# ALU.net
KiCad netlist of a schematic drawn in Altium Designer
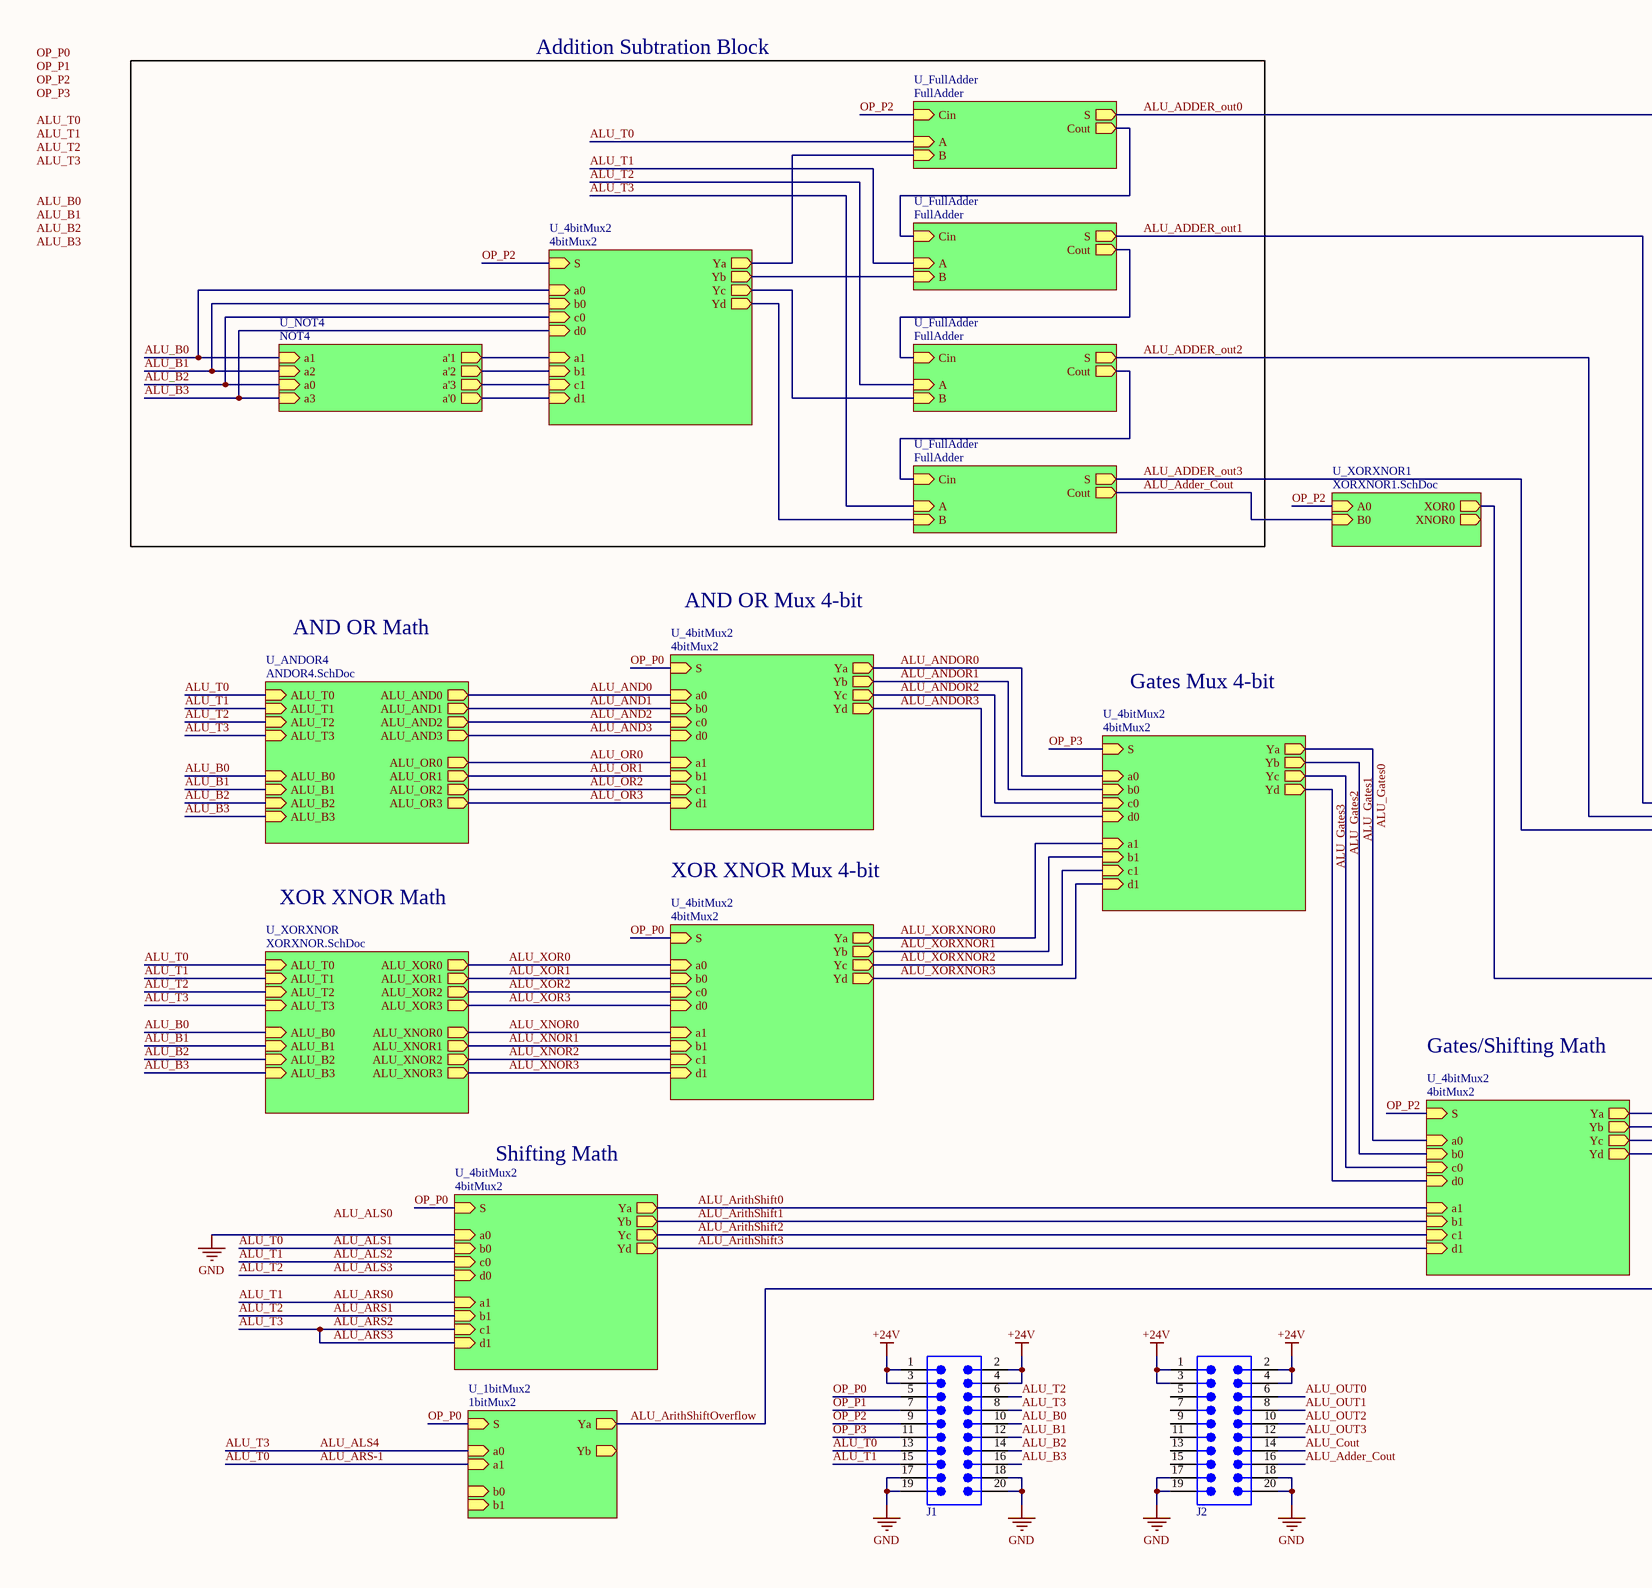
[diagram p0: ALU.SchDoc, left]
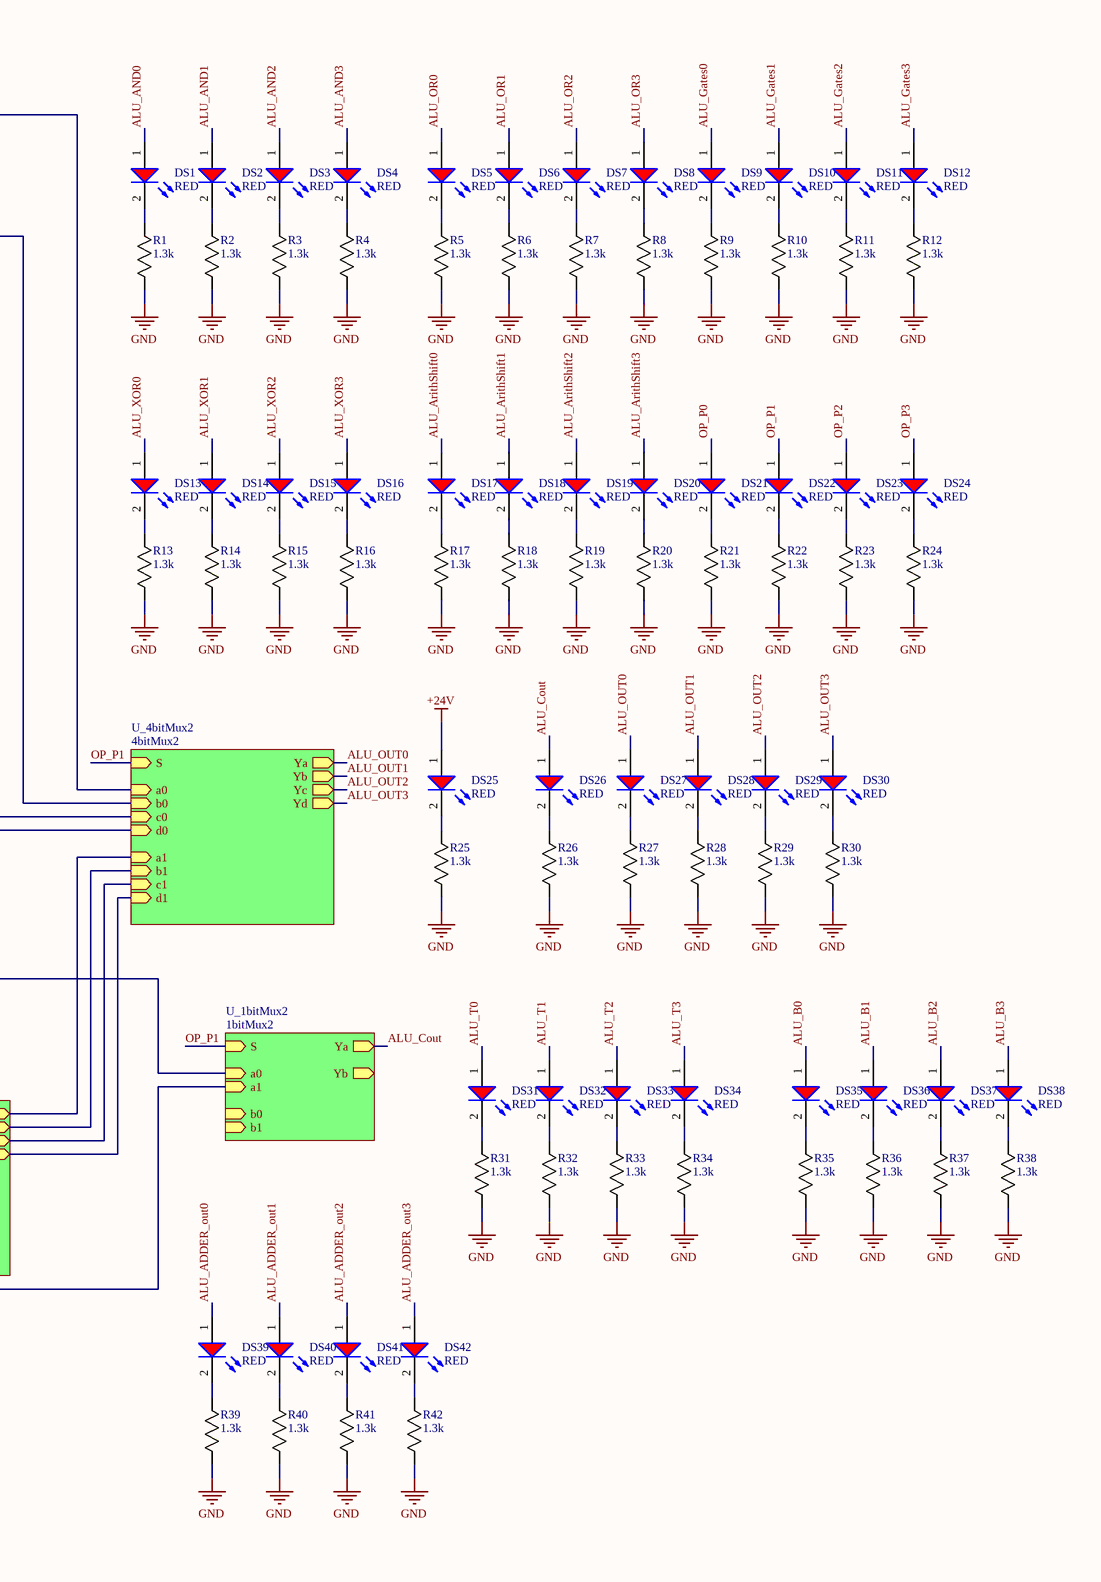
[diagram p1: ALU.SchDoc, right]

(export (version "E")
  (design (tool "Eeschema 10.0.6"))
  (components
    (comp (ref "DS1")
      (value "RED")
      (footprint "LED RED 151051RS11000")
      (description "WL-TMRC Red Color Diffused 5 mm Round Through Hole LED")
      (fields
        (field (name "MANUFACTURER") "Wurth Elektronik")
        (field (name "MANUFACTURER PART NUMBER") "151051RS11000")
      )
      (libsource (lib "Schlib1") (part "LED RED 151051RS11000"))
    )
    (comp (ref "DS2")
      (value "RED")
      (footprint "LED RED 151051RS11000")
      (description "WL-TMRC Red Color Diffused 5 mm Round Through Hole LED")
      (fields
        (field (name "MANUFACTURER") "Wurth Elektronik")
        (field (name "MANUFACTURER PART NUMBER") "151051RS11000")
      )
      (libsource (lib "Schlib1") (part "LED RED 151051RS11000"))
    )
    (comp (ref "DS3")
      (value "RED")
      (footprint "LED RED 151051RS11000")
      (description "WL-TMRC Red Color Diffused 5 mm Round Through Hole LED")
      (fields
        (field (name "MANUFACTURER") "Wurth Elektronik")
        (field (name "MANUFACTURER PART NUMBER") "151051RS11000")
      )
      (libsource (lib "Schlib1") (part "LED RED 151051RS11000"))
    )
    (comp (ref "DS4")
      (value "RED")
      (footprint "LED RED 151051RS11000")
      (description "WL-TMRC Red Color Diffused 5 mm Round Through Hole LED")
      (fields
        (field (name "MANUFACTURER") "Wurth Elektronik")
        (field (name "MANUFACTURER PART NUMBER") "151051RS11000")
      )
      (libsource (lib "Schlib1") (part "LED RED 151051RS11000"))
    )
    (comp (ref "DS5")
      (value "RED")
      (footprint "LED RED 151051RS11000")
      (description "WL-TMRC Red Color Diffused 5 mm Round Through Hole LED")
      (fields
        (field (name "MANUFACTURER") "Wurth Elektronik")
        (field (name "MANUFACTURER PART NUMBER") "151051RS11000")
      )
      (libsource (lib "Schlib1") (part "LED RED 151051RS11000"))
    )
    (comp (ref "DS6")
      (value "RED")
      (footprint "LED RED 151051RS11000")
      (description "WL-TMRC Red Color Diffused 5 mm Round Through Hole LED")
      (fields
        (field (name "MANUFACTURER") "Wurth Elektronik")
        (field (name "MANUFACTURER PART NUMBER") "151051RS11000")
      )
      (libsource (lib "Schlib1") (part "LED RED 151051RS11000"))
    )
    (comp (ref "DS7")
      (value "RED")
      (footprint "LED RED 151051RS11000")
      (description "WL-TMRC Red Color Diffused 5 mm Round Through Hole LED")
      (fields
        (field (name "MANUFACTURER") "Wurth Elektronik")
        (field (name "MANUFACTURER PART NUMBER") "151051RS11000")
      )
      (libsource (lib "Schlib1") (part "LED RED 151051RS11000"))
    )
    (comp (ref "DS8")
      (value "RED")
      (footprint "LED RED 151051RS11000")
      (description "WL-TMRC Red Color Diffused 5 mm Round Through Hole LED")
      (fields
        (field (name "MANUFACTURER") "Wurth Elektronik")
        (field (name "MANUFACTURER PART NUMBER") "151051RS11000")
      )
      (libsource (lib "Schlib1") (part "LED RED 151051RS11000"))
    )
    (comp (ref "DS9")
      (value "RED")
      (footprint "LED RED 151051RS11000")
      (description "WL-TMRC Red Color Diffused 5 mm Round Through Hole LED")
      (fields
        (field (name "MANUFACTURER") "Wurth Elektronik")
        (field (name "MANUFACTURER PART NUMBER") "151051RS11000")
      )
      (libsource (lib "Schlib1") (part "LED RED 151051RS11000"))
    )
    (comp (ref "DS10")
      (value "RED")
      (footprint "LED RED 151051RS11000")
      (description "WL-TMRC Red Color Diffused 5 mm Round Through Hole LED")
      (fields
        (field (name "MANUFACTURER") "Wurth Elektronik")
        (field (name "MANUFACTURER PART NUMBER") "151051RS11000")
      )
      (libsource (lib "Schlib1") (part "LED RED 151051RS11000"))
    )
    (comp (ref "DS11")
      (value "RED")
      (footprint "LED RED 151051RS11000")
      (description "WL-TMRC Red Color Diffused 5 mm Round Through Hole LED")
      (fields
        (field (name "MANUFACTURER") "Wurth Elektronik")
        (field (name "MANUFACTURER PART NUMBER") "151051RS11000")
      )
      (libsource (lib "Schlib1") (part "LED RED 151051RS11000"))
    )
    (comp (ref "DS12")
      (value "RED")
      (footprint "LED RED 151051RS11000")
      (description "WL-TMRC Red Color Diffused 5 mm Round Through Hole LED")
      (fields
        (field (name "MANUFACTURER") "Wurth Elektronik")
        (field (name "MANUFACTURER PART NUMBER") "151051RS11000")
      )
      (libsource (lib "Schlib1") (part "LED RED 151051RS11000"))
    )
    (comp (ref "DS13")
      (value "RED")
      (footprint "LED RED 151051RS11000")
      (description "WL-TMRC Red Color Diffused 5 mm Round Through Hole LED")
      (fields
        (field (name "MANUFACTURER") "Wurth Elektronik")
        (field (name "MANUFACTURER PART NUMBER") "151051RS11000")
      )
      (libsource (lib "Schlib1") (part "LED RED 151051RS11000"))
    )
    (comp (ref "DS14")
      (value "RED")
      (footprint "LED RED 151051RS11000")
      (description "WL-TMRC Red Color Diffused 5 mm Round Through Hole LED")
      (fields
        (field (name "MANUFACTURER") "Wurth Elektronik")
        (field (name "MANUFACTURER PART NUMBER") "151051RS11000")
      )
      (libsource (lib "Schlib1") (part "LED RED 151051RS11000"))
    )
    (comp (ref "DS15")
      (value "RED")
      (footprint "LED RED 151051RS11000")
      (description "WL-TMRC Red Color Diffused 5 mm Round Through Hole LED")
      (fields
        (field (name "MANUFACTURER") "Wurth Elektronik")
        (field (name "MANUFACTURER PART NUMBER") "151051RS11000")
      )
      (libsource (lib "Schlib1") (part "LED RED 151051RS11000"))
    )
    (comp (ref "DS16")
      (value "RED")
      (footprint "LED RED 151051RS11000")
      (description "WL-TMRC Red Color Diffused 5 mm Round Through Hole LED")
      (fields
        (field (name "MANUFACTURER") "Wurth Elektronik")
        (field (name "MANUFACTURER PART NUMBER") "151051RS11000")
      )
      (libsource (lib "Schlib1") (part "LED RED 151051RS11000"))
    )
    (comp (ref "DS17")
      (value "RED")
      (footprint "LED RED 151051RS11000")
      (description "WL-TMRC Red Color Diffused 5 mm Round Through Hole LED")
      (fields
        (field (name "MANUFACTURER") "Wurth Elektronik")
        (field (name "MANUFACTURER PART NUMBER") "151051RS11000")
      )
      (libsource (lib "Schlib1") (part "LED RED 151051RS11000"))
    )
    (comp (ref "DS18")
      (value "RED")
      (footprint "LED RED 151051RS11000")
      (description "WL-TMRC Red Color Diffused 5 mm Round Through Hole LED")
      (fields
        (field (name "MANUFACTURER") "Wurth Elektronik")
        (field (name "MANUFACTURER PART NUMBER") "151051RS11000")
      )
      (libsource (lib "Schlib1") (part "LED RED 151051RS11000"))
    )
    (comp (ref "DS19")
      (value "RED")
      (footprint "LED RED 151051RS11000")
      (description "WL-TMRC Red Color Diffused 5 mm Round Through Hole LED")
      (fields
        (field (name "MANUFACTURER") "Wurth Elektronik")
        (field (name "MANUFACTURER PART NUMBER") "151051RS11000")
      )
      (libsource (lib "Schlib1") (part "LED RED 151051RS11000"))
    )
    (comp (ref "DS20")
      (value "RED")
      (footprint "LED RED 151051RS11000")
      (description "WL-TMRC Red Color Diffused 5 mm Round Through Hole LED")
      (fields
        (field (name "MANUFACTURER") "Wurth Elektronik")
        (field (name "MANUFACTURER PART NUMBER") "151051RS11000")
      )
      (libsource (lib "Schlib1") (part "LED RED 151051RS11000"))
    )
    (comp (ref "DS21")
      (value "RED")
      (footprint "LED RED 151051RS11000")
      (description "WL-TMRC Red Color Diffused 5 mm Round Through Hole LED")
      (fields
        (field (name "MANUFACTURER") "Wurth Elektronik")
        (field (name "MANUFACTURER PART NUMBER") "151051RS11000")
      )
      (libsource (lib "Schlib1") (part "LED RED 151051RS11000"))
    )
    (comp (ref "DS22")
      (value "RED")
      (footprint "LED RED 151051RS11000")
      (description "WL-TMRC Red Color Diffused 5 mm Round Through Hole LED")
      (fields
        (field (name "MANUFACTURER") "Wurth Elektronik")
        (field (name "MANUFACTURER PART NUMBER") "151051RS11000")
      )
      (libsource (lib "Schlib1") (part "LED RED 151051RS11000"))
    )
    (comp (ref "DS23")
      (value "RED")
      (footprint "LED RED 151051RS11000")
      (description "WL-TMRC Red Color Diffused 5 mm Round Through Hole LED")
      (fields
        (field (name "MANUFACTURER") "Wurth Elektronik")
        (field (name "MANUFACTURER PART NUMBER") "151051RS11000")
      )
      (libsource (lib "Schlib1") (part "LED RED 151051RS11000"))
    )
    (comp (ref "DS24")
      (value "RED")
      (footprint "LED RED 151051RS11000")
      (description "WL-TMRC Red Color Diffused 5 mm Round Through Hole LED")
      (fields
        (field (name "MANUFACTURER") "Wurth Elektronik")
        (field (name "MANUFACTURER PART NUMBER") "151051RS11000")
      )
      (libsource (lib "Schlib1") (part "LED RED 151051RS11000"))
    )
    (comp (ref "DS25")
      (value "RED")
      (footprint "LED RED 151051RS11000")
      (description "WL-TMRC Red Color Diffused 5 mm Round Through Hole LED")
      (fields
        (field (name "MANUFACTURER") "Wurth Elektronik")
        (field (name "MANUFACTURER PART NUMBER") "151051RS11000")
      )
      (libsource (lib "Schlib1") (part "LED RED 151051RS11000"))
    )
    (comp (ref "DS26")
      (value "RED")
      (footprint "LED RED 151051RS11000")
      (description "WL-TMRC Red Color Diffused 5 mm Round Through Hole LED")
      (fields
        (field (name "MANUFACTURER") "Wurth Elektronik")
        (field (name "MANUFACTURER PART NUMBER") "151051RS11000")
      )
      (libsource (lib "Schlib1") (part "LED RED 151051RS11000"))
    )
    (comp (ref "DS27")
      (value "RED")
      (footprint "LED RED 151051RS11000")
      (description "WL-TMRC Red Color Diffused 5 mm Round Through Hole LED")
      (fields
        (field (name "MANUFACTURER") "Wurth Elektronik")
        (field (name "MANUFACTURER PART NUMBER") "151051RS11000")
      )
      (libsource (lib "Schlib1") (part "LED RED 151051RS11000"))
    )
    (comp (ref "DS28")
      (value "RED")
      (footprint "LED RED 151051RS11000")
      (description "WL-TMRC Red Color Diffused 5 mm Round Through Hole LED")
      (fields
        (field (name "MANUFACTURER") "Wurth Elektronik")
        (field (name "MANUFACTURER PART NUMBER") "151051RS11000")
      )
      (libsource (lib "Schlib1") (part "LED RED 151051RS11000"))
    )
    (comp (ref "DS29")
      (value "RED")
      (footprint "LED RED 151051RS11000")
      (description "WL-TMRC Red Color Diffused 5 mm Round Through Hole LED")
      (fields
        (field (name "MANUFACTURER") "Wurth Elektronik")
        (field (name "MANUFACTURER PART NUMBER") "151051RS11000")
      )
      (libsource (lib "Schlib1") (part "LED RED 151051RS11000"))
    )
    (comp (ref "DS30")
      (value "RED")
      (footprint "LED RED 151051RS11000")
      (description "WL-TMRC Red Color Diffused 5 mm Round Through Hole LED")
      (fields
        (field (name "MANUFACTURER") "Wurth Elektronik")
        (field (name "MANUFACTURER PART NUMBER") "151051RS11000")
      )
      (libsource (lib "Schlib1") (part "LED RED 151051RS11000"))
    )
    (comp (ref "DS31")
      (value "RED")
      (footprint "LED RED 151051RS11000")
      (description "WL-TMRC Red Color Diffused 5 mm Round Through Hole LED")
      (fields
        (field (name "MANUFACTURER") "Wurth Elektronik")
        (field (name "MANUFACTURER PART NUMBER") "151051RS11000")
      )
      (libsource (lib "Schlib1") (part "LED RED 151051RS11000"))
    )
    (comp (ref "DS32")
      (value "RED")
      (footprint "LED RED 151051RS11000")
      (description "WL-TMRC Red Color Diffused 5 mm Round Through Hole LED")
      (fields
        (field (name "MANUFACTURER") "Wurth Elektronik")
        (field (name "MANUFACTURER PART NUMBER") "151051RS11000")
      )
      (libsource (lib "Schlib1") (part "LED RED 151051RS11000"))
    )
    (comp (ref "DS33")
      (value "RED")
      (footprint "LED RED 151051RS11000")
      (description "WL-TMRC Red Color Diffused 5 mm Round Through Hole LED")
      (fields
        (field (name "MANUFACTURER") "Wurth Elektronik")
        (field (name "MANUFACTURER PART NUMBER") "151051RS11000")
      )
      (libsource (lib "Schlib1") (part "LED RED 151051RS11000"))
    )
    (comp (ref "DS34")
      (value "RED")
      (footprint "LED RED 151051RS11000")
      (description "WL-TMRC Red Color Diffused 5 mm Round Through Hole LED")
      (fields
        (field (name "MANUFACTURER") "Wurth Elektronik")
        (field (name "MANUFACTURER PART NUMBER") "151051RS11000")
      )
      (libsource (lib "Schlib1") (part "LED RED 151051RS11000"))
    )
    (comp (ref "DS35")
      (value "RED")
      (footprint "LED RED 151051RS11000")
      (description "WL-TMRC Red Color Diffused 5 mm Round Through Hole LED")
      (fields
        (field (name "MANUFACTURER") "Wurth Elektronik")
        (field (name "MANUFACTURER PART NUMBER") "151051RS11000")
      )
      (libsource (lib "Schlib1") (part "LED RED 151051RS11000"))
    )
    (comp (ref "DS36")
      (value "RED")
      (footprint "LED RED 151051RS11000")
      (description "WL-TMRC Red Color Diffused 5 mm Round Through Hole LED")
      (fields
        (field (name "MANUFACTURER") "Wurth Elektronik")
        (field (name "MANUFACTURER PART NUMBER") "151051RS11000")
      )
      (libsource (lib "Schlib1") (part "LED RED 151051RS11000"))
    )
    (comp (ref "DS37")
      (value "RED")
      (footprint "LED RED 151051RS11000")
      (description "WL-TMRC Red Color Diffused 5 mm Round Through Hole LED")
      (fields
        (field (name "MANUFACTURER") "Wurth Elektronik")
        (field (name "MANUFACTURER PART NUMBER") "151051RS11000")
      )
      (libsource (lib "Schlib1") (part "LED RED 151051RS11000"))
    )
    (comp (ref "DS38")
      (value "RED")
      (footprint "LED RED 151051RS11000")
      (description "WL-TMRC Red Color Diffused 5 mm Round Through Hole LED")
      (fields
        (field (name "MANUFACTURER") "Wurth Elektronik")
        (field (name "MANUFACTURER PART NUMBER") "151051RS11000")
      )
      (libsource (lib "Schlib1") (part "LED RED 151051RS11000"))
    )
    (comp (ref "DS39")
      (value "RED")
      (footprint "LED RED 151051RS11000")
      (description "WL-TMRC Red Color Diffused 5 mm Round Through Hole LED")
      (fields
        (field (name "MANUFACTURER") "Wurth Elektronik")
        (field (name "MANUFACTURER PART NUMBER") "151051RS11000")
      )
      (libsource (lib "Schlib1") (part "LED RED 151051RS11000"))
    )
    (comp (ref "DS40")
      (value "RED")
      (footprint "LED RED 151051RS11000")
      (description "WL-TMRC Red Color Diffused 5 mm Round Through Hole LED")
      (fields
        (field (name "MANUFACTURER") "Wurth Elektronik")
        (field (name "MANUFACTURER PART NUMBER") "151051RS11000")
      )
      (libsource (lib "Schlib1") (part "LED RED 151051RS11000"))
    )
    (comp (ref "DS41")
      (value "RED")
      (footprint "LED RED 151051RS11000")
      (description "WL-TMRC Red Color Diffused 5 mm Round Through Hole LED")
      (fields
        (field (name "MANUFACTURER") "Wurth Elektronik")
        (field (name "MANUFACTURER PART NUMBER") "151051RS11000")
      )
      (libsource (lib "Schlib1") (part "LED RED 151051RS11000"))
    )
    (comp (ref "DS42")
      (value "RED")
      (footprint "LED RED 151051RS11000")
      (description "WL-TMRC Red Color Diffused 5 mm Round Through Hole LED")
      (fields
        (field (name "MANUFACTURER") "Wurth Elektronik")
        (field (name "MANUFACTURER PART NUMBER") "151051RS11000")
      )
      (libsource (lib "Schlib1") (part "LED RED 151051RS11000"))
    )
    (comp (ref "J1")
      (value "Con 61202021621")
      (footprint "Con 61202021621")
      (description "WR-BHD Straight Male, Box Header, Through Hole, 2 Rows, 20 Contacts, 2.54mm Pitch")
      (fields
        (field (name "MANUFACTURER") "Wurth Elektronik")
        (field (name "MANUFACTURER PART NUMBER") "61202021621")
      )
      (libsource (lib "Schlib1") (part "Con 61202021621"))
    )
    (comp (ref "J2")
      (value "Con 61202021621")
      (footprint "Con 61202021621")
      (description "WR-BHD Straight Male, Box Header, Through Hole, 2 Rows, 20 Contacts, 2.54mm Pitch")
      (fields
        (field (name "MANUFACTURER") "Wurth Elektronik")
        (field (name "MANUFACTURER PART NUMBER") "61202021621")
      )
      (libsource (lib "Schlib1") (part "Con 61202021621"))
    )
    (comp (ref "R1")
      (value "1.3k")
      (footprint "RES 2512")
      (description "Res Thick Film 2512 1.3K Ohm 1% 1W ±100ppm/C Pad SMD Automotive T/R RMCF2512FT1K30")
      (fields
        (field (name "MANUFACTURER") "Stackpole Electronics")
        (field (name "MANUFACTURER PART NUMBER") "RMCF2512FT1K30")
      )
      (libsource (lib "Schlib1") (part "RES 1.3k 2512 1W"))
    )
    (comp (ref "R2")
      (value "1.3k")
      (footprint "RES 2512")
      (description "Res Thick Film 2512 1.3K Ohm 1% 1W ±100ppm/C Pad SMD Automotive T/R RMCF2512FT1K30")
      (fields
        (field (name "MANUFACTURER") "Stackpole Electronics")
        (field (name "MANUFACTURER PART NUMBER") "RMCF2512FT1K30")
      )
      (libsource (lib "Schlib1") (part "RES 1.3k 2512 1W"))
    )
    (comp (ref "R3")
      (value "1.3k")
      (footprint "RES 2512")
      (description "Res Thick Film 2512 1.3K Ohm 1% 1W ±100ppm/C Pad SMD Automotive T/R RMCF2512FT1K30")
      (fields
        (field (name "MANUFACTURER") "Stackpole Electronics")
        (field (name "MANUFACTURER PART NUMBER") "RMCF2512FT1K30")
      )
      (libsource (lib "Schlib1") (part "RES 1.3k 2512 1W"))
    )
    (comp (ref "R4")
      (value "1.3k")
      (footprint "RES 2512")
      (description "Res Thick Film 2512 1.3K Ohm 1% 1W ±100ppm/C Pad SMD Automotive T/R RMCF2512FT1K30")
      (fields
        (field (name "MANUFACTURER") "Stackpole Electronics")
        (field (name "MANUFACTURER PART NUMBER") "RMCF2512FT1K30")
      )
      (libsource (lib "Schlib1") (part "RES 1.3k 2512 1W"))
    )
    (comp (ref "R5")
      (value "1.3k")
      (footprint "RES 2512")
      (description "Res Thick Film 2512 1.3K Ohm 1% 1W ±100ppm/C Pad SMD Automotive T/R RMCF2512FT1K30")
      (fields
        (field (name "MANUFACTURER") "Stackpole Electronics")
        (field (name "MANUFACTURER PART NUMBER") "RMCF2512FT1K30")
      )
      (libsource (lib "Schlib1") (part "RES 1.3k 2512 1W"))
    )
    (comp (ref "R6")
      (value "1.3k")
      (footprint "RES 2512")
      (description "Res Thick Film 2512 1.3K Ohm 1% 1W ±100ppm/C Pad SMD Automotive T/R RMCF2512FT1K30")
      (fields
        (field (name "MANUFACTURER") "Stackpole Electronics")
        (field (name "MANUFACTURER PART NUMBER") "RMCF2512FT1K30")
      )
      (libsource (lib "Schlib1") (part "RES 1.3k 2512 1W"))
    )
    (comp (ref "R7")
      (value "1.3k")
      (footprint "RES 2512")
      (description "Res Thick Film 2512 1.3K Ohm 1% 1W ±100ppm/C Pad SMD Automotive T/R RMCF2512FT1K30")
      (fields
        (field (name "MANUFACTURER") "Stackpole Electronics")
        (field (name "MANUFACTURER PART NUMBER") "RMCF2512FT1K30")
      )
      (libsource (lib "Schlib1") (part "RES 1.3k 2512 1W"))
    )
    (comp (ref "R8")
      (value "1.3k")
      (footprint "RES 2512")
      (description "Res Thick Film 2512 1.3K Ohm 1% 1W ±100ppm/C Pad SMD Automotive T/R RMCF2512FT1K30")
      (fields
        (field (name "MANUFACTURER") "Stackpole Electronics")
        (field (name "MANUFACTURER PART NUMBER") "RMCF2512FT1K30")
      )
      (libsource (lib "Schlib1") (part "RES 1.3k 2512 1W"))
    )
    (comp (ref "R9")
      (value "1.3k")
      (footprint "RES 2512")
      (description "Res Thick Film 2512 1.3K Ohm 1% 1W ±100ppm/C Pad SMD Automotive T/R RMCF2512FT1K30")
      (fields
        (field (name "MANUFACTURER") "Stackpole Electronics")
        (field (name "MANUFACTURER PART NUMBER") "RMCF2512FT1K30")
      )
      (libsource (lib "Schlib1") (part "RES 1.3k 2512 1W"))
    )
    (comp (ref "R10")
      (value "1.3k")
      (footprint "RES 2512")
      (description "Res Thick Film 2512 1.3K Ohm 1% 1W ±100ppm/C Pad SMD Automotive T/R RMCF2512FT1K30")
      (fields
        (field (name "MANUFACTURER") "Stackpole Electronics")
        (field (name "MANUFACTURER PART NUMBER") "RMCF2512FT1K30")
      )
      (libsource (lib "Schlib1") (part "RES 1.3k 2512 1W"))
    )
    (comp (ref "R11")
      (value "1.3k")
      (footprint "RES 2512")
      (description "Res Thick Film 2512 1.3K Ohm 1% 1W ±100ppm/C Pad SMD Automotive T/R RMCF2512FT1K30")
      (fields
        (field (name "MANUFACTURER") "Stackpole Electronics")
        (field (name "MANUFACTURER PART NUMBER") "RMCF2512FT1K30")
      )
      (libsource (lib "Schlib1") (part "RES 1.3k 2512 1W"))
    )
    (comp (ref "R12")
      (value "1.3k")
      (footprint "RES 2512")
      (description "Res Thick Film 2512 1.3K Ohm 1% 1W ±100ppm/C Pad SMD Automotive T/R RMCF2512FT1K30")
      (fields
        (field (name "MANUFACTURER") "Stackpole Electronics")
        (field (name "MANUFACTURER PART NUMBER") "RMCF2512FT1K30")
      )
      (libsource (lib "Schlib1") (part "RES 1.3k 2512 1W"))
    )
    (comp (ref "R13")
      (value "1.3k")
      (footprint "RES 2512")
      (description "Res Thick Film 2512 1.3K Ohm 1% 1W ±100ppm/C Pad SMD Automotive T/R RMCF2512FT1K30")
      (fields
        (field (name "MANUFACTURER") "Stackpole Electronics")
        (field (name "MANUFACTURER PART NUMBER") "RMCF2512FT1K30")
      )
      (libsource (lib "Schlib1") (part "RES 1.3k 2512 1W"))
    )
    (comp (ref "R14")
      (value "1.3k")
      (footprint "RES 2512")
      (description "Res Thick Film 2512 1.3K Ohm 1% 1W ±100ppm/C Pad SMD Automotive T/R RMCF2512FT1K30")
      (fields
        (field (name "MANUFACTURER") "Stackpole Electronics")
        (field (name "MANUFACTURER PART NUMBER") "RMCF2512FT1K30")
      )
      (libsource (lib "Schlib1") (part "RES 1.3k 2512 1W"))
    )
    (comp (ref "R15")
      (value "1.3k")
      (footprint "RES 2512")
      (description "Res Thick Film 2512 1.3K Ohm 1% 1W ±100ppm/C Pad SMD Automotive T/R RMCF2512FT1K30")
      (fields
        (field (name "MANUFACTURER") "Stackpole Electronics")
        (field (name "MANUFACTURER PART NUMBER") "RMCF2512FT1K30")
      )
      (libsource (lib "Schlib1") (part "RES 1.3k 2512 1W"))
    )
    (comp (ref "R16")
      (value "1.3k")
      (footprint "RES 2512")
      (description "Res Thick Film 2512 1.3K Ohm 1% 1W ±100ppm/C Pad SMD Automotive T/R RMCF2512FT1K30")
      (fields
        (field (name "MANUFACTURER") "Stackpole Electronics")
        (field (name "MANUFACTURER PART NUMBER") "RMCF2512FT1K30")
      )
      (libsource (lib "Schlib1") (part "RES 1.3k 2512 1W"))
    )
    (comp (ref "R17")
      (value "1.3k")
      (footprint "RES 2512")
      (description "Res Thick Film 2512 1.3K Ohm 1% 1W ±100ppm/C Pad SMD Automotive T/R RMCF2512FT1K30")
      (fields
        (field (name "MANUFACTURER") "Stackpole Electronics")
        (field (name "MANUFACTURER PART NUMBER") "RMCF2512FT1K30")
      )
      (libsource (lib "Schlib1") (part "RES 1.3k 2512 1W"))
    )
    (comp (ref "R18")
      (value "1.3k")
      (footprint "RES 2512")
      (description "Res Thick Film 2512 1.3K Ohm 1% 1W ±100ppm/C Pad SMD Automotive T/R RMCF2512FT1K30")
      (fields
        (field (name "MANUFACTURER") "Stackpole Electronics")
        (field (name "MANUFACTURER PART NUMBER") "RMCF2512FT1K30")
      )
      (libsource (lib "Schlib1") (part "RES 1.3k 2512 1W"))
    )
    (comp (ref "R19")
      (value "1.3k")
      (footprint "RES 2512")
      (description "Res Thick Film 2512 1.3K Ohm 1% 1W ±100ppm/C Pad SMD Automotive T/R RMCF2512FT1K30")
      (fields
        (field (name "MANUFACTURER") "Stackpole Electronics")
        (field (name "MANUFACTURER PART NUMBER") "RMCF2512FT1K30")
      )
      (libsource (lib "Schlib1") (part "RES 1.3k 2512 1W"))
    )
    (comp (ref "R20")
      (value "1.3k")
      (footprint "RES 2512")
      (description "Res Thick Film 2512 1.3K Ohm 1% 1W ±100ppm/C Pad SMD Automotive T/R RMCF2512FT1K30")
      (fields
        (field (name "MANUFACTURER") "Stackpole Electronics")
        (field (name "MANUFACTURER PART NUMBER") "RMCF2512FT1K30")
      )
      (libsource (lib "Schlib1") (part "RES 1.3k 2512 1W"))
    )
    (comp (ref "R21")
      (value "1.3k")
      (footprint "RES 2512")
      (description "Res Thick Film 2512 1.3K Ohm 1% 1W ±100ppm/C Pad SMD Automotive T/R RMCF2512FT1K30")
      (fields
        (field (name "MANUFACTURER") "Stackpole Electronics")
        (field (name "MANUFACTURER PART NUMBER") "RMCF2512FT1K30")
      )
      (libsource (lib "Schlib1") (part "RES 1.3k 2512 1W"))
    )
    (comp (ref "R22")
      (value "1.3k")
      (footprint "RES 2512")
      (description "Res Thick Film 2512 1.3K Ohm 1% 1W ±100ppm/C Pad SMD Automotive T/R RMCF2512FT1K30")
      (fields
        (field (name "MANUFACTURER") "Stackpole Electronics")
        (field (name "MANUFACTURER PART NUMBER") "RMCF2512FT1K30")
      )
      (libsource (lib "Schlib1") (part "RES 1.3k 2512 1W"))
    )
    (comp (ref "R23")
      (value "1.3k")
      (footprint "RES 2512")
      (description "Res Thick Film 2512 1.3K Ohm 1% 1W ±100ppm/C Pad SMD Automotive T/R RMCF2512FT1K30")
      (fields
        (field (name "MANUFACTURER") "Stackpole Electronics")
        (field (name "MANUFACTURER PART NUMBER") "RMCF2512FT1K30")
      )
      (libsource (lib "Schlib1") (part "RES 1.3k 2512 1W"))
    )
    (comp (ref "R24")
      (value "1.3k")
      (footprint "RES 2512")
      (description "Res Thick Film 2512 1.3K Ohm 1% 1W ±100ppm/C Pad SMD Automotive T/R RMCF2512FT1K30")
      (fields
        (field (name "MANUFACTURER") "Stackpole Electronics")
        (field (name "MANUFACTURER PART NUMBER") "RMCF2512FT1K30")
      )
      (libsource (lib "Schlib1") (part "RES 1.3k 2512 1W"))
    )
    (comp (ref "R25")
      (value "1.3k")
      (footprint "RES 2512")
      (description "Res Thick Film 2512 1.3K Ohm 1% 1W ±100ppm/C Pad SMD Automotive T/R RMCF2512FT1K30")
      (fields
        (field (name "MANUFACTURER") "Stackpole Electronics")
        (field (name "MANUFACTURER PART NUMBER") "RMCF2512FT1K30")
      )
      (libsource (lib "Schlib1") (part "RES 1.3k 2512 1W"))
    )
    (comp (ref "R26")
      (value "1.3k")
      (footprint "RES 2512")
      (description "Res Thick Film 2512 1.3K Ohm 1% 1W ±100ppm/C Pad SMD Automotive T/R RMCF2512FT1K30")
      (fields
        (field (name "MANUFACTURER") "Stackpole Electronics")
        (field (name "MANUFACTURER PART NUMBER") "RMCF2512FT1K30")
      )
      (libsource (lib "Schlib1") (part "RES 1.3k 2512 1W"))
    )
    (comp (ref "R27")
      (value "1.3k")
      (footprint "RES 2512")
      (description "Res Thick Film 2512 1.3K Ohm 1% 1W ±100ppm/C Pad SMD Automotive T/R RMCF2512FT1K30")
      (fields
        (field (name "MANUFACTURER") "Stackpole Electronics")
        (field (name "MANUFACTURER PART NUMBER") "RMCF2512FT1K30")
      )
      (libsource (lib "Schlib1") (part "RES 1.3k 2512 1W"))
    )
    (comp (ref "R28")
      (value "1.3k")
      (footprint "RES 2512")
      (description "Res Thick Film 2512 1.3K Ohm 1% 1W ±100ppm/C Pad SMD Automotive T/R RMCF2512FT1K30")
      (fields
        (field (name "MANUFACTURER") "Stackpole Electronics")
        (field (name "MANUFACTURER PART NUMBER") "RMCF2512FT1K30")
      )
      (libsource (lib "Schlib1") (part "RES 1.3k 2512 1W"))
    )
    (comp (ref "R29")
      (value "1.3k")
      (footprint "RES 2512")
      (description "Res Thick Film 2512 1.3K Ohm 1% 1W ±100ppm/C Pad SMD Automotive T/R RMCF2512FT1K30")
      (fields
        (field (name "MANUFACTURER") "Stackpole Electronics")
        (field (name "MANUFACTURER PART NUMBER") "RMCF2512FT1K30")
      )
      (libsource (lib "Schlib1") (part "RES 1.3k 2512 1W"))
    )
    (comp (ref "R30")
      (value "1.3k")
      (footprint "RES 2512")
      (description "Res Thick Film 2512 1.3K Ohm 1% 1W ±100ppm/C Pad SMD Automotive T/R RMCF2512FT1K30")
      (fields
        (field (name "MANUFACTURER") "Stackpole Electronics")
        (field (name "MANUFACTURER PART NUMBER") "RMCF2512FT1K30")
      )
      (libsource (lib "Schlib1") (part "RES 1.3k 2512 1W"))
    )
    (comp (ref "R31")
      (value "1.3k")
      (footprint "RES 2512")
      (description "Res Thick Film 2512 1.3K Ohm 1% 1W ±100ppm/C Pad SMD Automotive T/R RMCF2512FT1K30")
      (fields
        (field (name "MANUFACTURER") "Stackpole Electronics")
        (field (name "MANUFACTURER PART NUMBER") "RMCF2512FT1K30")
      )
      (libsource (lib "Schlib1") (part "RES 1.3k 2512 1W"))
    )
    (comp (ref "R32")
      (value "1.3k")
      (footprint "RES 2512")
      (description "Res Thick Film 2512 1.3K Ohm 1% 1W ±100ppm/C Pad SMD Automotive T/R RMCF2512FT1K30")
      (fields
        (field (name "MANUFACTURER") "Stackpole Electronics")
        (field (name "MANUFACTURER PART NUMBER") "RMCF2512FT1K30")
      )
      (libsource (lib "Schlib1") (part "RES 1.3k 2512 1W"))
    )
    (comp (ref "R33")
      (value "1.3k")
      (footprint "RES 2512")
      (description "Res Thick Film 2512 1.3K Ohm 1% 1W ±100ppm/C Pad SMD Automotive T/R RMCF2512FT1K30")
      (fields
        (field (name "MANUFACTURER") "Stackpole Electronics")
        (field (name "MANUFACTURER PART NUMBER") "RMCF2512FT1K30")
      )
      (libsource (lib "Schlib1") (part "RES 1.3k 2512 1W"))
    )
    (comp (ref "R34")
      (value "1.3k")
      (footprint "RES 2512")
      (description "Res Thick Film 2512 1.3K Ohm 1% 1W ±100ppm/C Pad SMD Automotive T/R RMCF2512FT1K30")
      (fields
        (field (name "MANUFACTURER") "Stackpole Electronics")
        (field (name "MANUFACTURER PART NUMBER") "RMCF2512FT1K30")
      )
      (libsource (lib "Schlib1") (part "RES 1.3k 2512 1W"))
    )
    (comp (ref "R35")
      (value "1.3k")
      (footprint "RES 2512")
      (description "Res Thick Film 2512 1.3K Ohm 1% 1W ±100ppm/C Pad SMD Automotive T/R RMCF2512FT1K30")
      (fields
        (field (name "MANUFACTURER") "Stackpole Electronics")
        (field (name "MANUFACTURER PART NUMBER") "RMCF2512FT1K30")
      )
      (libsource (lib "Schlib1") (part "RES 1.3k 2512 1W"))
    )
    (comp (ref "R36")
      (value "1.3k")
      (footprint "RES 2512")
      (description "Res Thick Film 2512 1.3K Ohm 1% 1W ±100ppm/C Pad SMD Automotive T/R RMCF2512FT1K30")
      (fields
        (field (name "MANUFACTURER") "Stackpole Electronics")
        (field (name "MANUFACTURER PART NUMBER") "RMCF2512FT1K30")
      )
      (libsource (lib "Schlib1") (part "RES 1.3k 2512 1W"))
    )
    (comp (ref "R37")
      (value "1.3k")
      (footprint "RES 2512")
      (description "Res Thick Film 2512 1.3K Ohm 1% 1W ±100ppm/C Pad SMD Automotive T/R RMCF2512FT1K30")
      (fields
        (field (name "MANUFACTURER") "Stackpole Electronics")
        (field (name "MANUFACTURER PART NUMBER") "RMCF2512FT1K30")
      )
      (libsource (lib "Schlib1") (part "RES 1.3k 2512 1W"))
    )
    (comp (ref "R38")
      (value "1.3k")
      (footprint "RES 2512")
      (description "Res Thick Film 2512 1.3K Ohm 1% 1W ±100ppm/C Pad SMD Automotive T/R RMCF2512FT1K30")
      (fields
        (field (name "MANUFACTURER") "Stackpole Electronics")
        (field (name "MANUFACTURER PART NUMBER") "RMCF2512FT1K30")
      )
      (libsource (lib "Schlib1") (part "RES 1.3k 2512 1W"))
    )
    (comp (ref "R39")
      (value "1.3k")
      (footprint "RES 2512")
      (description "Res Thick Film 2512 1.3K Ohm 1% 1W ±100ppm/C Pad SMD Automotive T/R RMCF2512FT1K30")
      (fields
        (field (name "MANUFACTURER") "Stackpole Electronics")
        (field (name "MANUFACTURER PART NUMBER") "RMCF2512FT1K30")
      )
      (libsource (lib "Schlib1") (part "RES 1.3k 2512 1W"))
    )
    (comp (ref "R40")
      (value "1.3k")
      (footprint "RES 2512")
      (description "Res Thick Film 2512 1.3K Ohm 1% 1W ±100ppm/C Pad SMD Automotive T/R RMCF2512FT1K30")
      (fields
        (field (name "MANUFACTURER") "Stackpole Electronics")
        (field (name "MANUFACTURER PART NUMBER") "RMCF2512FT1K30")
      )
      (libsource (lib "Schlib1") (part "RES 1.3k 2512 1W"))
    )
    (comp (ref "R41")
      (value "1.3k")
      (footprint "RES 2512")
      (description "Res Thick Film 2512 1.3K Ohm 1% 1W ±100ppm/C Pad SMD Automotive T/R RMCF2512FT1K30")
      (fields
        (field (name "MANUFACTURER") "Stackpole Electronics")
        (field (name "MANUFACTURER PART NUMBER") "RMCF2512FT1K30")
      )
      (libsource (lib "Schlib1") (part "RES 1.3k 2512 1W"))
    )
    (comp (ref "R42")
      (value "1.3k")
      (footprint "RES 2512")
      (description "Res Thick Film 2512 1.3K Ohm 1% 1W ±100ppm/C Pad SMD Automotive T/R RMCF2512FT1K30")
      (fields
        (field (name "MANUFACTURER") "Stackpole Electronics")
        (field (name "MANUFACTURER PART NUMBER") "RMCF2512FT1K30")
      )
      (libsource (lib "Schlib1") (part "RES 1.3k 2512 1W"))
    )
  )
  (nets
    (net (code "1") (name "+24V") (class "Default")
      (node (ref "DS25") (pin "1") (pinfunction "A_1") (pintype "passive"))
      (node (ref "J1") (pin "1") (pinfunction "1_1") (pintype "passive"))
      (node (ref "J1") (pin "2") (pinfunction "2_2") (pintype "passive"))
      (node (ref "J1") (pin "3") (pinfunction "3_3") (pintype "passive"))
      (node (ref "J1") (pin "4") (pinfunction "4_4") (pintype "passive"))
      (node (ref "J2") (pin "1") (pinfunction "1_1") (pintype "passive"))
      (node (ref "J2") (pin "2") (pinfunction "2_2") (pintype "passive"))
      (node (ref "J2") (pin "3") (pinfunction "3_3") (pintype "passive"))
      (node (ref "J2") (pin "4") (pinfunction "4_4") (pintype "passive"))
    )
    (net (code "2") (name "/ALU_ADDER_out0") (class "Default")
      (node (ref "DS39") (pin "1") (pinfunction "A_1") (pintype "passive"))
    )
    (net (code "3") (name "/ALU_ADDER_out1") (class "Default")
      (node (ref "DS40") (pin "1") (pinfunction "A_1") (pintype "passive"))
    )
    (net (code "4") (name "/ALU_ADDER_out2") (class "Default")
      (node (ref "DS41") (pin "1") (pinfunction "A_1") (pintype "passive"))
    )
    (net (code "5") (name "/ALU_ADDER_out3") (class "Default")
      (node (ref "DS42") (pin "1") (pinfunction "A_1") (pintype "passive"))
    )
    (net (code "7") (name "/ALU_ALS1") (class "Default")
      (node (ref "DS31") (pin "1") (pinfunction "A_1") (pintype "passive"))
      (node (ref "J1") (pin "13") (pinfunction "13_13") (pintype "passive"))
    )
    (net (code "8") (name "/ALU_ALS2") (class "Default")
      (node (ref "DS32") (pin "1") (pinfunction "A_1") (pintype "passive"))
      (node (ref "J1") (pin "15") (pinfunction "15_15") (pintype "passive"))
    )
    (net (code "9") (name "/ALU_ALS3") (class "Default")
      (node (ref "DS33") (pin "1") (pinfunction "A_1") (pintype "passive"))
      (node (ref "J1") (pin "6") (pinfunction "6_6") (pintype "passive"))
    )
    (net (code "10") (name "/ALU_ALS4") (class "Default")
      (node (ref "DS34") (pin "1") (pinfunction "A_1") (pintype "passive"))
      (node (ref "J1") (pin "8") (pinfunction "8_8") (pintype "passive"))
    )
    (net (code "11") (name "/ALU_AND0") (class "Default")
      (node (ref "DS1") (pin "1") (pinfunction "A_1") (pintype "passive"))
    )
    (net (code "12") (name "/ALU_AND1") (class "Default")
      (node (ref "DS2") (pin "1") (pinfunction "A_1") (pintype "passive"))
    )
    (net (code "13") (name "/ALU_AND2") (class "Default")
      (node (ref "DS3") (pin "1") (pinfunction "A_1") (pintype "passive"))
    )
    (net (code "14") (name "/ALU_AND3") (class "Default")
      (node (ref "DS4") (pin "1") (pinfunction "A_1") (pintype "passive"))
    )
    (net (code "19") (name "/ALU_Adder_Cout") (class "Default")
      (node (ref "J2") (pin "16") (pinfunction "16_16") (pintype "passive"))
    )
    (net (code "20") (name "/ALU_ArithShift0") (class "Default")
      (node (ref "DS17") (pin "1") (pinfunction "A_1") (pintype "passive"))
    )
    (net (code "21") (name "/ALU_ArithShift1") (class "Default")
      (node (ref "DS18") (pin "1") (pinfunction "A_1") (pintype "passive"))
    )
    (net (code "22") (name "/ALU_ArithShift2") (class "Default")
      (node (ref "DS19") (pin "1") (pinfunction "A_1") (pintype "passive"))
    )
    (net (code "23") (name "/ALU_ArithShift3") (class "Default")
      (node (ref "DS20") (pin "1") (pinfunction "A_1") (pintype "passive"))
    )
    (net (code "25") (name "/ALU_B0") (class "Default")
      (node (ref "DS35") (pin "1") (pinfunction "A_1") (pintype "passive"))
      (node (ref "J1") (pin "10") (pinfunction "10_10") (pintype "passive"))
    )
    (net (code "26") (name "/ALU_B1") (class "Default")
      (node (ref "DS36") (pin "1") (pinfunction "A_1") (pintype "passive"))
      (node (ref "J1") (pin "12") (pinfunction "12_12") (pintype "passive"))
    )
    (net (code "27") (name "/ALU_B2") (class "Default")
      (node (ref "DS37") (pin "1") (pinfunction "A_1") (pintype "passive"))
      (node (ref "J1") (pin "14") (pinfunction "14_14") (pintype "passive"))
    )
    (net (code "28") (name "/ALU_B3") (class "Default")
      (node (ref "DS38") (pin "1") (pinfunction "A_1") (pintype "passive"))
      (node (ref "J1") (pin "16") (pinfunction "16_16") (pintype "passive"))
    )
    (net (code "29") (name "/ALU_Cout") (class "Default")
      (node (ref "DS26") (pin "1") (pinfunction "A_1") (pintype "passive"))
      (node (ref "J2") (pin "14") (pinfunction "14_14") (pintype "passive"))
    )
    (net (code "30") (name "/ALU_Gates0") (class "Default")
      (node (ref "DS9") (pin "1") (pinfunction "A_1") (pintype "passive"))
    )
    (net (code "31") (name "/ALU_Gates1") (class "Default")
      (node (ref "DS10") (pin "1") (pinfunction "A_1") (pintype "passive"))
    )
    (net (code "32") (name "/ALU_Gates2") (class "Default")
      (node (ref "DS11") (pin "1") (pinfunction "A_1") (pintype "passive"))
    )
    (net (code "33") (name "/ALU_Gates3") (class "Default")
      (node (ref "DS12") (pin "1") (pinfunction "A_1") (pintype "passive"))
    )
    (net (code "34") (name "/ALU_OR0") (class "Default")
      (node (ref "DS5") (pin "1") (pinfunction "A_1") (pintype "passive"))
    )
    (net (code "35") (name "/ALU_OR1") (class "Default")
      (node (ref "DS6") (pin "1") (pinfunction "A_1") (pintype "passive"))
    )
    (net (code "36") (name "/ALU_OR2") (class "Default")
      (node (ref "DS7") (pin "1") (pinfunction "A_1") (pintype "passive"))
    )
    (net (code "37") (name "/ALU_OR3") (class "Default")
      (node (ref "DS8") (pin "1") (pinfunction "A_1") (pintype "passive"))
    )
    (net (code "38") (name "/ALU_OUT0") (class "Default")
      (node (ref "DS27") (pin "1") (pinfunction "A_1") (pintype "passive"))
      (node (ref "J2") (pin "6") (pinfunction "6_6") (pintype "passive"))
    )
    (net (code "39") (name "/ALU_OUT1") (class "Default")
      (node (ref "DS28") (pin "1") (pinfunction "A_1") (pintype "passive"))
      (node (ref "J2") (pin "8") (pinfunction "8_8") (pintype "passive"))
    )
    (net (code "40") (name "/ALU_OUT2") (class "Default")
      (node (ref "DS29") (pin "1") (pinfunction "A_1") (pintype "passive"))
      (node (ref "J2") (pin "10") (pinfunction "10_10") (pintype "passive"))
    )
    (net (code "41") (name "/ALU_OUT3") (class "Default")
      (node (ref "DS30") (pin "1") (pinfunction "A_1") (pintype "passive"))
      (node (ref "J2") (pin "12") (pinfunction "12_12") (pintype "passive"))
    )
    (net (code "46") (name "/ALU_XOR0") (class "Default")
      (node (ref "DS13") (pin "1") (pinfunction "A_1") (pintype "passive"))
    )
    (net (code "47") (name "/ALU_XOR1") (class "Default")
      (node (ref "DS14") (pin "1") (pinfunction "A_1") (pintype "passive"))
    )
    (net (code "48") (name "/ALU_XOR2") (class "Default")
      (node (ref "DS15") (pin "1") (pinfunction "A_1") (pintype "passive"))
    )
    (net (code "49") (name "/ALU_XOR3") (class "Default")
      (node (ref "DS16") (pin "1") (pinfunction "A_1") (pintype "passive"))
    )
    (net (code "57") (name "/OP_P0") (class "Default")
      (node (ref "DS21") (pin "1") (pinfunction "A_1") (pintype "passive"))
      (node (ref "J1") (pin "5") (pinfunction "5_5") (pintype "passive"))
    )
    (net (code "58") (name "/OP_P1") (class "Default")
      (node (ref "DS22") (pin "1") (pinfunction "A_1") (pintype "passive"))
      (node (ref "J1") (pin "7") (pinfunction "7_7") (pintype "passive"))
    )
    (net (code "59") (name "/OP_P2") (class "Default")
      (node (ref "DS23") (pin "1") (pinfunction "A_1") (pintype "passive"))
      (node (ref "J1") (pin "9") (pinfunction "9_9") (pintype "passive"))
    )
    (net (code "60") (name "/OP_P3") (class "Default")
      (node (ref "DS24") (pin "1") (pinfunction "A_1") (pintype "passive"))
      (node (ref "J1") (pin "11") (pinfunction "11_11") (pintype "passive"))
    )
    (net (code "81") (name "GND") (class "Default")
      (node (ref "J1") (pin "17") (pinfunction "17_17") (pintype "passive"))
      (node (ref "J1") (pin "18") (pinfunction "18_18") (pintype "passive"))
      (node (ref "J1") (pin "19") (pinfunction "19_19") (pintype "passive"))
      (node (ref "J1") (pin "20") (pinfunction "20_20") (pintype "passive"))
      (node (ref "J2") (pin "17") (pinfunction "17_17") (pintype "passive"))
      (node (ref "J2") (pin "18") (pinfunction "18_18") (pintype "passive"))
      (node (ref "J2") (pin "19") (pinfunction "19_19") (pintype "passive"))
      (node (ref "J2") (pin "20") (pinfunction "20_20") (pintype "passive"))
      (node (ref "R1") (pin "2") (pinfunction "2_2") (pintype "passive"))
      (node (ref "R10") (pin "2") (pinfunction "2_2") (pintype "passive"))
      (node (ref "R11") (pin "2") (pinfunction "2_2") (pintype "passive"))
      (node (ref "R12") (pin "2") (pinfunction "2_2") (pintype "passive"))
      (node (ref "R13") (pin "2") (pinfunction "2_2") (pintype "passive"))
      (node (ref "R14") (pin "2") (pinfunction "2_2") (pintype "passive"))
      (node (ref "R15") (pin "2") (pinfunction "2_2") (pintype "passive"))
      (node (ref "R16") (pin "2") (pinfunction "2_2") (pintype "passive"))
      (node (ref "R17") (pin "2") (pinfunction "2_2") (pintype "passive"))
      (node (ref "R18") (pin "2") (pinfunction "2_2") (pintype "passive"))
      (node (ref "R19") (pin "2") (pinfunction "2_2") (pintype "passive"))
      (node (ref "R2") (pin "2") (pinfunction "2_2") (pintype "passive"))
      (node (ref "R20") (pin "2") (pinfunction "2_2") (pintype "passive"))
      (node (ref "R21") (pin "2") (pinfunction "2_2") (pintype "passive"))
      (node (ref "R22") (pin "2") (pinfunction "2_2") (pintype "passive"))
      (node (ref "R23") (pin "2") (pinfunction "2_2") (pintype "passive"))
      (node (ref "R24") (pin "2") (pinfunction "2_2") (pintype "passive"))
      (node (ref "R25") (pin "2") (pinfunction "2_2") (pintype "passive"))
      (node (ref "R26") (pin "2") (pinfunction "2_2") (pintype "passive"))
      (node (ref "R27") (pin "2") (pinfunction "2_2") (pintype "passive"))
      (node (ref "R28") (pin "2") (pinfunction "2_2") (pintype "passive"))
      (node (ref "R29") (pin "2") (pinfunction "2_2") (pintype "passive"))
      (node (ref "R3") (pin "2") (pinfunction "2_2") (pintype "passive"))
      (node (ref "R30") (pin "2") (pinfunction "2_2") (pintype "passive"))
      (node (ref "R31") (pin "2") (pinfunction "2_2") (pintype "passive"))
      (node (ref "R32") (pin "2") (pinfunction "2_2") (pintype "passive"))
      (node (ref "R33") (pin "2") (pinfunction "2_2") (pintype "passive"))
      (node (ref "R34") (pin "2") (pinfunction "2_2") (pintype "passive"))
      (node (ref "R35") (pin "2") (pinfunction "2_2") (pintype "passive"))
      (node (ref "R36") (pin "2") (pinfunction "2_2") (pintype "passive"))
      (node (ref "R37") (pin "2") (pinfunction "2_2") (pintype "passive"))
      (node (ref "R38") (pin "2") (pinfunction "2_2") (pintype "passive"))
      (node (ref "R39") (pin "2") (pinfunction "2_2") (pintype "passive"))
      (node (ref "R4") (pin "2") (pinfunction "2_2") (pintype "passive"))
      (node (ref "R40") (pin "2") (pinfunction "2_2") (pintype "passive"))
      (node (ref "R41") (pin "2") (pinfunction "2_2") (pintype "passive"))
      (node (ref "R42") (pin "2") (pinfunction "2_2") (pintype "passive"))
      (node (ref "R5") (pin "2") (pinfunction "2_2") (pintype "passive"))
      (node (ref "R6") (pin "2") (pinfunction "2_2") (pintype "passive"))
      (node (ref "R7") (pin "2") (pinfunction "2_2") (pintype "passive"))
      (node (ref "R8") (pin "2") (pinfunction "2_2") (pintype "passive"))
      (node (ref "R9") (pin "2") (pinfunction "2_2") (pintype "passive"))
    )
    (net (code "82") (name "Net-(DS1-K)") (class "Default")
      (node (ref "DS1") (pin "2") (pinfunction "K_2") (pintype "passive"))
      (node (ref "R1") (pin "1") (pinfunction "1_1") (pintype "passive"))
    )
    (net (code "83") (name "Net-(DS2-K)") (class "Default")
      (node (ref "DS2") (pin "2") (pinfunction "K_2") (pintype "passive"))
      (node (ref "R2") (pin "1") (pinfunction "1_1") (pintype "passive"))
    )
    (net (code "84") (name "Net-(DS3-K)") (class "Default")
      (node (ref "DS3") (pin "2") (pinfunction "K_2") (pintype "passive"))
      (node (ref "R3") (pin "1") (pinfunction "1_1") (pintype "passive"))
    )
    (net (code "85") (name "Net-(DS4-K)") (class "Default")
      (node (ref "DS4") (pin "2") (pinfunction "K_2") (pintype "passive"))
      (node (ref "R4") (pin "1") (pinfunction "1_1") (pintype "passive"))
    )
    (net (code "86") (name "Net-(DS5-K)") (class "Default")
      (node (ref "DS5") (pin "2") (pinfunction "K_2") (pintype "passive"))
      (node (ref "R5") (pin "1") (pinfunction "1_1") (pintype "passive"))
    )
    (net (code "87") (name "Net-(DS6-K)") (class "Default")
      (node (ref "DS6") (pin "2") (pinfunction "K_2") (pintype "passive"))
      (node (ref "R6") (pin "1") (pinfunction "1_1") (pintype "passive"))
    )
    (net (code "88") (name "Net-(DS7-K)") (class "Default")
      (node (ref "DS7") (pin "2") (pinfunction "K_2") (pintype "passive"))
      (node (ref "R7") (pin "1") (pinfunction "1_1") (pintype "passive"))
    )
    (net (code "89") (name "Net-(DS8-K)") (class "Default")
      (node (ref "DS8") (pin "2") (pinfunction "K_2") (pintype "passive"))
      (node (ref "R8") (pin "1") (pinfunction "1_1") (pintype "passive"))
    )
    (net (code "90") (name "Net-(DS9-K)") (class "Default")
      (node (ref "DS9") (pin "2") (pinfunction "K_2") (pintype "passive"))
      (node (ref "R9") (pin "1") (pinfunction "1_1") (pintype "passive"))
    )
    (net (code "91") (name "Net-(DS10-K)") (class "Default")
      (node (ref "DS10") (pin "2") (pinfunction "K_2") (pintype "passive"))
      (node (ref "R10") (pin "1") (pinfunction "1_1") (pintype "passive"))
    )
    (net (code "92") (name "Net-(DS11-K)") (class "Default")
      (node (ref "DS11") (pin "2") (pinfunction "K_2") (pintype "passive"))
      (node (ref "R11") (pin "1") (pinfunction "1_1") (pintype "passive"))
    )
    (net (code "93") (name "Net-(DS12-K)") (class "Default")
      (node (ref "DS12") (pin "2") (pinfunction "K_2") (pintype "passive"))
      (node (ref "R12") (pin "1") (pinfunction "1_1") (pintype "passive"))
    )
    (net (code "94") (name "Net-(DS13-K)") (class "Default")
      (node (ref "DS13") (pin "2") (pinfunction "K_2") (pintype "passive"))
      (node (ref "R13") (pin "1") (pinfunction "1_1") (pintype "passive"))
    )
    (net (code "95") (name "Net-(DS14-K)") (class "Default")
      (node (ref "DS14") (pin "2") (pinfunction "K_2") (pintype "passive"))
      (node (ref "R14") (pin "1") (pinfunction "1_1") (pintype "passive"))
    )
    (net (code "96") (name "Net-(DS15-K)") (class "Default")
      (node (ref "DS15") (pin "2") (pinfunction "K_2") (pintype "passive"))
      (node (ref "R15") (pin "1") (pinfunction "1_1") (pintype "passive"))
    )
    (net (code "97") (name "Net-(DS16-K)") (class "Default")
      (node (ref "DS16") (pin "2") (pinfunction "K_2") (pintype "passive"))
      (node (ref "R16") (pin "1") (pinfunction "1_1") (pintype "passive"))
    )
    (net (code "98") (name "Net-(DS17-K)") (class "Default")
      (node (ref "DS17") (pin "2") (pinfunction "K_2") (pintype "passive"))
      (node (ref "R17") (pin "1") (pinfunction "1_1") (pintype "passive"))
    )
    (net (code "99") (name "Net-(DS18-K)") (class "Default")
      (node (ref "DS18") (pin "2") (pinfunction "K_2") (pintype "passive"))
      (node (ref "R18") (pin "1") (pinfunction "1_1") (pintype "passive"))
    )
    (net (code "100") (name "Net-(DS19-K)") (class "Default")
      (node (ref "DS19") (pin "2") (pinfunction "K_2") (pintype "passive"))
      (node (ref "R19") (pin "1") (pinfunction "1_1") (pintype "passive"))
    )
    (net (code "101") (name "Net-(DS20-K)") (class "Default")
      (node (ref "DS20") (pin "2") (pinfunction "K_2") (pintype "passive"))
      (node (ref "R20") (pin "1") (pinfunction "1_1") (pintype "passive"))
    )
    (net (code "102") (name "Net-(DS21-K)") (class "Default")
      (node (ref "DS21") (pin "2") (pinfunction "K_2") (pintype "passive"))
      (node (ref "R21") (pin "1") (pinfunction "1_1") (pintype "passive"))
    )
    (net (code "103") (name "Net-(DS22-K)") (class "Default")
      (node (ref "DS22") (pin "2") (pinfunction "K_2") (pintype "passive"))
      (node (ref "R22") (pin "1") (pinfunction "1_1") (pintype "passive"))
    )
    (net (code "104") (name "Net-(DS23-K)") (class "Default")
      (node (ref "DS23") (pin "2") (pinfunction "K_2") (pintype "passive"))
      (node (ref "R23") (pin "1") (pinfunction "1_1") (pintype "passive"))
    )
    (net (code "105") (name "Net-(DS24-K)") (class "Default")
      (node (ref "DS24") (pin "2") (pinfunction "K_2") (pintype "passive"))
      (node (ref "R24") (pin "1") (pinfunction "1_1") (pintype "passive"))
    )
    (net (code "106") (name "Net-(DS25-K)") (class "Default")
      (node (ref "DS25") (pin "2") (pinfunction "K_2") (pintype "passive"))
      (node (ref "R25") (pin "1") (pinfunction "1_1") (pintype "passive"))
    )
    (net (code "107") (name "Net-(DS26-K)") (class "Default")
      (node (ref "DS26") (pin "2") (pinfunction "K_2") (pintype "passive"))
      (node (ref "R26") (pin "1") (pinfunction "1_1") (pintype "passive"))
    )
    (net (code "108") (name "Net-(DS27-K)") (class "Default")
      (node (ref "DS27") (pin "2") (pinfunction "K_2") (pintype "passive"))
      (node (ref "R27") (pin "1") (pinfunction "1_1") (pintype "passive"))
    )
    (net (code "109") (name "Net-(DS28-K)") (class "Default")
      (node (ref "DS28") (pin "2") (pinfunction "K_2") (pintype "passive"))
      (node (ref "R28") (pin "1") (pinfunction "1_1") (pintype "passive"))
    )
    (net (code "110") (name "Net-(DS29-K)") (class "Default")
      (node (ref "DS29") (pin "2") (pinfunction "K_2") (pintype "passive"))
      (node (ref "R29") (pin "1") (pinfunction "1_1") (pintype "passive"))
    )
    (net (code "111") (name "Net-(DS30-K)") (class "Default")
      (node (ref "DS30") (pin "2") (pinfunction "K_2") (pintype "passive"))
      (node (ref "R30") (pin "1") (pinfunction "1_1") (pintype "passive"))
    )
    (net (code "112") (name "Net-(DS31-K)") (class "Default")
      (node (ref "DS31") (pin "2") (pinfunction "K_2") (pintype "passive"))
      (node (ref "R31") (pin "1") (pinfunction "1_1") (pintype "passive"))
    )
    (net (code "113") (name "Net-(DS32-K)") (class "Default")
      (node (ref "DS32") (pin "2") (pinfunction "K_2") (pintype "passive"))
      (node (ref "R32") (pin "1") (pinfunction "1_1") (pintype "passive"))
    )
    (net (code "114") (name "Net-(DS33-K)") (class "Default")
      (node (ref "DS33") (pin "2") (pinfunction "K_2") (pintype "passive"))
      (node (ref "R33") (pin "1") (pinfunction "1_1") (pintype "passive"))
    )
    (net (code "115") (name "Net-(DS34-K)") (class "Default")
      (node (ref "DS34") (pin "2") (pinfunction "K_2") (pintype "passive"))
      (node (ref "R34") (pin "1") (pinfunction "1_1") (pintype "passive"))
    )
    (net (code "116") (name "Net-(DS35-K)") (class "Default")
      (node (ref "DS35") (pin "2") (pinfunction "K_2") (pintype "passive"))
      (node (ref "R35") (pin "1") (pinfunction "1_1") (pintype "passive"))
    )
    (net (code "117") (name "Net-(DS36-K)") (class "Default")
      (node (ref "DS36") (pin "2") (pinfunction "K_2") (pintype "passive"))
      (node (ref "R36") (pin "1") (pinfunction "1_1") (pintype "passive"))
    )
    (net (code "118") (name "Net-(DS37-K)") (class "Default")
      (node (ref "DS37") (pin "2") (pinfunction "K_2") (pintype "passive"))
      (node (ref "R37") (pin "1") (pinfunction "1_1") (pintype "passive"))
    )
    (net (code "119") (name "Net-(DS38-K)") (class "Default")
      (node (ref "DS38") (pin "2") (pinfunction "K_2") (pintype "passive"))
      (node (ref "R38") (pin "1") (pinfunction "1_1") (pintype "passive"))
    )
    (net (code "120") (name "Net-(DS39-K)") (class "Default")
      (node (ref "DS39") (pin "2") (pinfunction "K_2") (pintype "passive"))
      (node (ref "R39") (pin "1") (pinfunction "1_1") (pintype "passive"))
    )
    (net (code "121") (name "Net-(DS40-K)") (class "Default")
      (node (ref "DS40") (pin "2") (pinfunction "K_2") (pintype "passive"))
      (node (ref "R40") (pin "1") (pinfunction "1_1") (pintype "passive"))
    )
    (net (code "122") (name "Net-(DS41-K)") (class "Default")
      (node (ref "DS41") (pin "2") (pinfunction "K_2") (pintype "passive"))
      (node (ref "R41") (pin "1") (pinfunction "1_1") (pintype "passive"))
    )
    (net (code "123") (name "Net-(DS42-K)") (class "Default")
      (node (ref "DS42") (pin "2") (pinfunction "K_2") (pintype "passive"))
      (node (ref "R42") (pin "1") (pinfunction "1_1") (pintype "passive"))
    )
    (net (code "124") (name "unconnected-(J2-Pad5)") (class "Default")
      (node (ref "J2") (pin "5") (pinfunction "5_5") (pintype "passive"))
    )
    (net (code "125") (name "unconnected-(J2-Pad7)") (class "Default")
      (node (ref "J2") (pin "7") (pinfunction "7_7") (pintype "passive"))
    )
    (net (code "126") (name "unconnected-(J2-Pad9)") (class "Default")
      (node (ref "J2") (pin "9") (pinfunction "9_9") (pintype "passive"))
    )
    (net (code "127") (name "unconnected-(J2-Pad11)") (class "Default")
      (node (ref "J2") (pin "11") (pinfunction "11_11") (pintype "passive"))
    )
    (net (code "128") (name "unconnected-(J2-Pad13)") (class "Default")
      (node (ref "J2") (pin "13") (pinfunction "13_13") (pintype "passive"))
    )
    (net (code "129") (name "unconnected-(J2-Pad15)") (class "Default")
      (node (ref "J2") (pin "15") (pinfunction "15_15") (pintype "passive"))
    )
  )
)
